# STM32G4.net
KiCad netlist of a schematic drawn in Altium Designer
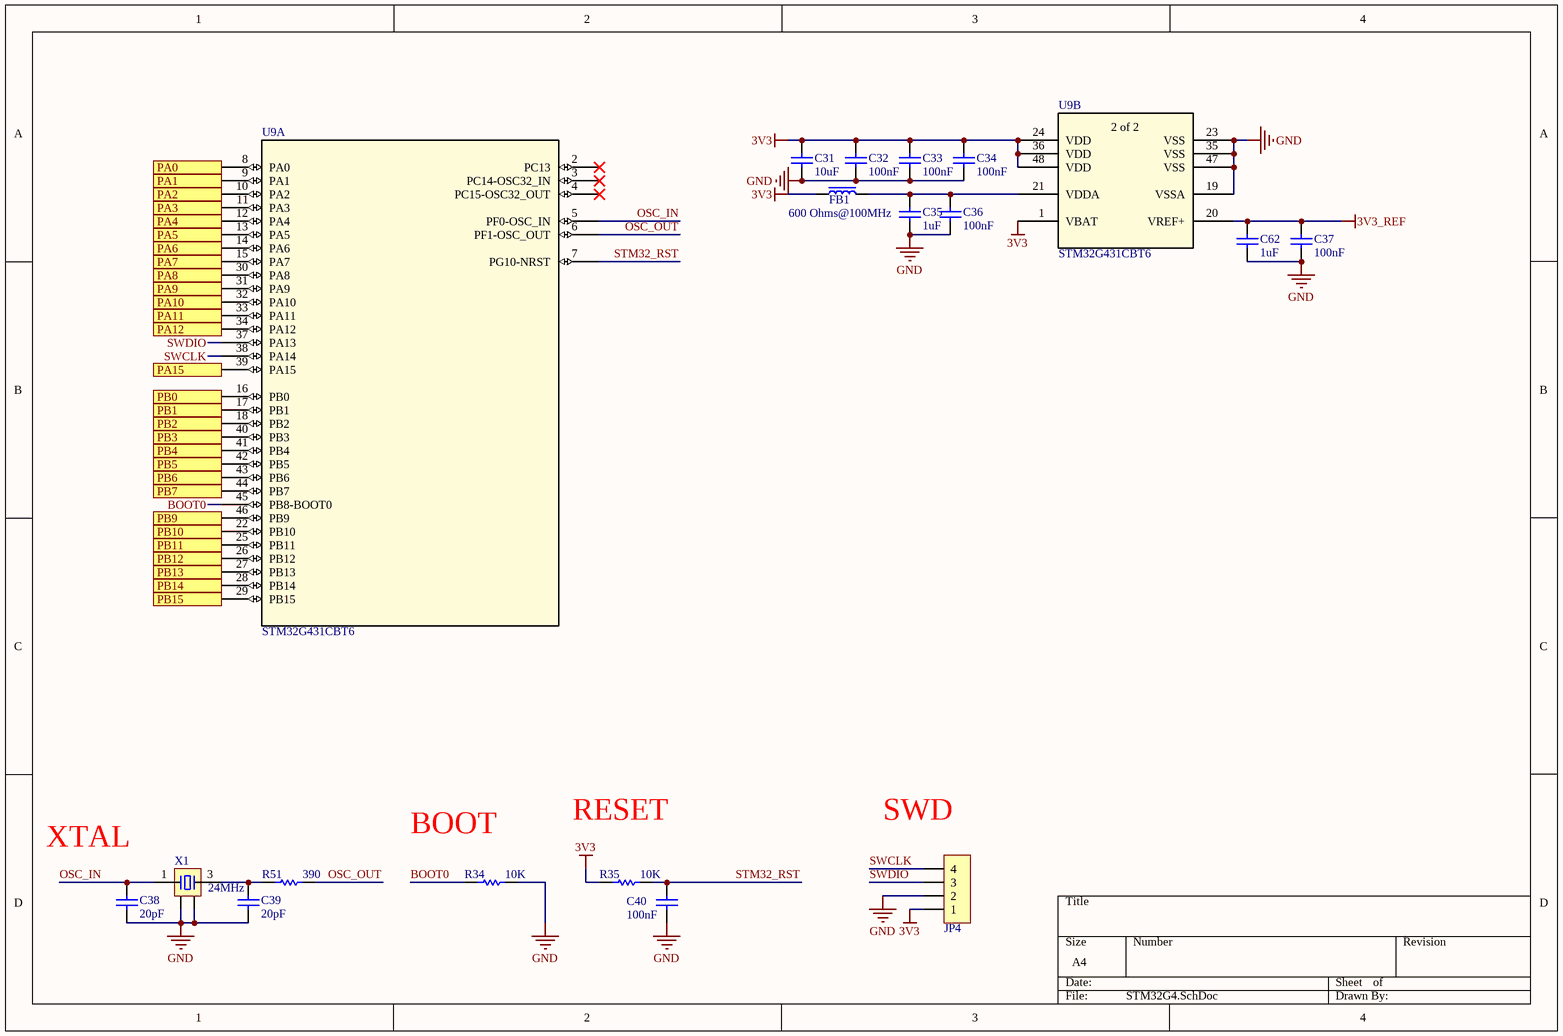
[diagram p0: STM32G4.SchDoc]

(export (version "E")
  (design (tool "Eeschema 10.0.6"))
  (components
    (comp (ref "C31") (value "10uF") (footprint "C0805") (libsource (lib "Cap") (part "Cap")))
    (comp (ref "C32") (value "100nF") (footprint "C0402") (libsource (lib "Cap") (part "Cap")))
    (comp (ref "C33") (value "100nF") (footprint "C0402") (libsource (lib "Cap") (part "Cap")))
    (comp (ref "C34") (value "100nF") (footprint "C0402") (libsource (lib "Cap") (part "Cap")))
    (comp (ref "C35") (value "1uF") (footprint "C0603") (libsource (lib "Cap") (part "Cap")))
    (comp (ref "C36") (value "100nF") (footprint "C0402") (libsource (lib "Cap") (part "Cap")))
    (comp (ref "C37") (value "100nF") (footprint "C0402") (libsource (lib "Cap") (part "Cap")))
    (comp (ref "C38") (value "20pF") (footprint "C0402") (libsource (lib "Cap") (part "Cap")))
    (comp (ref "C39") (value "20pF") (footprint "C0402") (libsource (lib "Cap") (part "Cap")))
    (comp (ref "C40") (value "100nF") (footprint "C0402") (libsource (lib "Cap") (part "Cap")))
    (comp (ref "C62") (value "1uF") (footprint "C0603") (libsource (lib "Cap") (part "Cap")))
    (comp (ref "FB1")
      (value "600 Ohms@100MHz")
      (footprint "FB 0402")
      (description "磁珠")
      (libsource (lib "All lib") (part "FB"))
    )
    (comp (ref "JP4")
      (value "HDR-1X4")
      (footprint "XH2.54-4P_H")
      (description "4P接插件")
      (fields (field (name "版权归属") "源创客"))
      (libsource (lib "All lib") (part "Header 4P"))
    )
    (comp (ref "R34") (value "10K") (footprint "R0402") (libsource (lib "Res") (part "RES")))
    (comp (ref "R35") (value "10K") (footprint "R0402") (libsource (lib "Res") (part "RES")))
    (comp (ref "R51") (value "390") (footprint "R0402") (libsource (lib "Res") (part "RES")))
    (comp (ref "U9")
      (value "STM32G431CBT6")
      (footprint "LQFP48 7X7_L")
      (description "No Description Available")
      (fields (field (name "COPYRIGHT") "Copyright (C) 2022 Ultra Librarian. All rights reserved."))
      (libsource (lib "All lib") (part "STM32G431CBT6"))
    )
    (comp (ref "X1")
      (value "24MHz")
      (footprint "XTAL-3225")
      (description "4脚晶振")
      (fields (field (name "版权归属") "源创客"))
      (libsource (lib "All lib") (part "XTAL-4"))
    )
  )
  (nets
    (net (code "1") (name "/BOOT0") (class "Default")
      (node (ref "R34") (pin "1") (pinfunction "1_1") (pintype "passive"))
      (node (ref "U9") (pin "45") (pinfunction "PB8-BOOT0_45") (pintype "bidirectional"))
    )
    (net (code "2") (name "/OSC_IN") (class "Default")
      (node (ref "C38") (pin "2") (pinfunction "2_2") (pintype "passive"))
      (node (ref "U9") (pin "5") (pinfunction "PF0-OSC_IN_5") (pintype "bidirectional"))
      (node (ref "X1") (pin "1") (pinfunction "1_1") (pintype "passive"))
    )
    (net (code "3") (name "/OSC_OUT") (class "Default")
      (node (ref "R51") (pin "2") (pinfunction "2_2") (pintype "passive"))
      (node (ref "U9") (pin "6") (pinfunction "PF1-OSC_OUT_6") (pintype "bidirectional"))
    )
    (net (code "4") (name "/PA0") (class "Default")
      (node (ref "U9") (pin "8") (pinfunction "PA0_8") (pintype "bidirectional"))
    )
    (net (code "5") (name "/PA1") (class "Default")
      (node (ref "U9") (pin "9") (pinfunction "PA1_9") (pintype "bidirectional"))
    )
    (net (code "6") (name "/PA2") (class "Default")
      (node (ref "U9") (pin "10") (pinfunction "PA2_10") (pintype "bidirectional"))
    )
    (net (code "7") (name "/PA3") (class "Default")
      (node (ref "U9") (pin "11") (pinfunction "PA3_11") (pintype "bidirectional"))
    )
    (net (code "8") (name "/PA4") (class "Default")
      (node (ref "U9") (pin "12") (pinfunction "PA4_12") (pintype "bidirectional"))
    )
    (net (code "9") (name "/PA5") (class "Default")
      (node (ref "U9") (pin "13") (pinfunction "PA5_13") (pintype "bidirectional"))
    )
    (net (code "10") (name "/PA6") (class "Default")
      (node (ref "U9") (pin "14") (pinfunction "PA6_14") (pintype "bidirectional"))
    )
    (net (code "11") (name "/PA7") (class "Default")
      (node (ref "U9") (pin "15") (pinfunction "PA7_15") (pintype "bidirectional"))
    )
    (net (code "12") (name "/PA8") (class "Default")
      (node (ref "U9") (pin "30") (pinfunction "PA8_30") (pintype "bidirectional"))
    )
    (net (code "13") (name "/PA9") (class "Default")
      (node (ref "U9") (pin "31") (pinfunction "PA9_31") (pintype "bidirectional"))
    )
    (net (code "14") (name "/PA10") (class "Default")
      (node (ref "U9") (pin "32") (pinfunction "PA10_32") (pintype "bidirectional"))
    )
    (net (code "15") (name "/PA11") (class "Default")
      (node (ref "U9") (pin "33") (pinfunction "PA11_33") (pintype "bidirectional"))
    )
    (net (code "16") (name "/PA12") (class "Default")
      (node (ref "U9") (pin "34") (pinfunction "PA12_34") (pintype "bidirectional"))
    )
    (net (code "17") (name "/PA15") (class "Default")
      (node (ref "U9") (pin "39") (pinfunction "PA15_39") (pintype "bidirectional"))
    )
    (net (code "18") (name "/PB0") (class "Default")
      (node (ref "U9") (pin "16") (pinfunction "PB0_16") (pintype "bidirectional"))
    )
    (net (code "19") (name "/PB1") (class "Default")
      (node (ref "U9") (pin "17") (pinfunction "PB1_17") (pintype "bidirectional"))
    )
    (net (code "20") (name "/PB2") (class "Default")
      (node (ref "U9") (pin "18") (pinfunction "PB2_18") (pintype "bidirectional"))
    )
    (net (code "21") (name "/PB3") (class "Default")
      (node (ref "U9") (pin "40") (pinfunction "PB3_40") (pintype "bidirectional"))
    )
    (net (code "22") (name "/PB4") (class "Default")
      (node (ref "U9") (pin "41") (pinfunction "PB4_41") (pintype "bidirectional"))
    )
    (net (code "23") (name "/PB5") (class "Default")
      (node (ref "U9") (pin "42") (pinfunction "PB5_42") (pintype "bidirectional"))
    )
    (net (code "24") (name "/PB6") (class "Default")
      (node (ref "U9") (pin "43") (pinfunction "PB6_43") (pintype "bidirectional"))
    )
    (net (code "25") (name "/PB7") (class "Default")
      (node (ref "U9") (pin "44") (pinfunction "PB7_44") (pintype "bidirectional"))
    )
    (net (code "26") (name "/PB9") (class "Default")
      (node (ref "U9") (pin "46") (pinfunction "PB9_46") (pintype "bidirectional"))
    )
    (net (code "27") (name "/PB10") (class "Default")
      (node (ref "U9") (pin "22") (pinfunction "PB10_22") (pintype "bidirectional"))
    )
    (net (code "28") (name "/PB11") (class "Default")
      (node (ref "U9") (pin "25") (pinfunction "PB11_25") (pintype "bidirectional"))
    )
    (net (code "29") (name "/PB12") (class "Default")
      (node (ref "U9") (pin "26") (pinfunction "PB12_26") (pintype "bidirectional"))
    )
    (net (code "30") (name "/PB13") (class "Default")
      (node (ref "U9") (pin "27") (pinfunction "PB13_27") (pintype "bidirectional"))
    )
    (net (code "31") (name "/PB14") (class "Default")
      (node (ref "U9") (pin "28") (pinfunction "PB14_28") (pintype "bidirectional"))
    )
    (net (code "32") (name "/PB15") (class "Default")
      (node (ref "U9") (pin "29") (pinfunction "PB15_29") (pintype "bidirectional"))
    )
    (net (code "33") (name "/STM32_RST") (class "Default")
      (node (ref "C40") (pin "2") (pinfunction "2_2") (pintype "passive"))
      (node (ref "R35") (pin "2") (pinfunction "2_2") (pintype "passive"))
      (node (ref "U9") (pin "7") (pinfunction "PG10-NRST_7") (pintype "bidirectional"))
    )
    (net (code "34") (name "/SWCLK") (class "Default")
      (node (ref "JP4") (pin "4") (pinfunction "4_4") (pintype "passive"))
      (node (ref "U9") (pin "38") (pinfunction "PA14_38") (pintype "bidirectional"))
    )
    (net (code "35") (name "/SWDIO") (class "Default")
      (node (ref "JP4") (pin "3") (pinfunction "3_3") (pintype "passive"))
      (node (ref "U9") (pin "37") (pinfunction "PA13_37") (pintype "bidirectional"))
    )
    (net (code "36") (name "3V3") (class "Default")
      (node (ref "C31") (pin "2") (pinfunction "2_2") (pintype "passive"))
      (node (ref "C32") (pin "2") (pinfunction "2_2") (pintype "passive"))
      (node (ref "C33") (pin "2") (pinfunction "2_2") (pintype "passive"))
      (node (ref "C34") (pin "2") (pinfunction "2_2") (pintype "passive"))
      (node (ref "FB1") (pin "1") (pinfunction "1_1") (pintype "passive"))
      (node (ref "JP4") (pin "1") (pinfunction "1_1") (pintype "passive"))
      (node (ref "R35") (pin "1") (pinfunction "1_1") (pintype "passive"))
      (node (ref "U9") (pin "1") (pinfunction "VBAT_1") (pintype "power_in"))
      (node (ref "U9") (pin "24") (pinfunction "VDD_24") (pintype "power_in"))
      (node (ref "U9") (pin "36") (pinfunction "VDD_36") (pintype "power_in"))
      (node (ref "U9") (pin "48") (pinfunction "VDD_48") (pintype "power_in"))
    )
    (net (code "37") (name "3V3_REF") (class "Default")
      (node (ref "C37") (pin "1") (pinfunction "1_1") (pintype "passive"))
      (node (ref "C62") (pin "1") (pinfunction "1_1") (pintype "passive"))
      (node (ref "U9") (pin "20") (pinfunction "VREF+_20") (pintype "power_in"))
    )
    (net (code "38") (name "GND") (class "Default")
      (node (ref "C31") (pin "1") (pinfunction "1_1") (pintype "passive"))
      (node (ref "C32") (pin "1") (pinfunction "1_1") (pintype "passive"))
      (node (ref "C33") (pin "1") (pinfunction "1_1") (pintype "passive"))
      (node (ref "C34") (pin "1") (pinfunction "1_1") (pintype "passive"))
      (node (ref "C35") (pin "2") (pinfunction "2_2") (pintype "passive"))
      (node (ref "C36") (pin "2") (pinfunction "2_2") (pintype "passive"))
      (node (ref "C37") (pin "2") (pinfunction "2_2") (pintype "passive"))
      (node (ref "C38") (pin "1") (pinfunction "1_1") (pintype "passive"))
      (node (ref "C39") (pin "1") (pinfunction "1_1") (pintype "passive"))
      (node (ref "C40") (pin "1") (pinfunction "1_1") (pintype "passive"))
      (node (ref "C62") (pin "2") (pinfunction "2_2") (pintype "passive"))
      (node (ref "JP4") (pin "2") (pinfunction "2_2") (pintype "passive"))
      (node (ref "R34") (pin "2") (pinfunction "2_2") (pintype "passive"))
      (node (ref "U9") (pin "19") (pinfunction "VSSA_19") (pintype "power_in"))
      (node (ref "U9") (pin "23") (pinfunction "VSS_23") (pintype "power_in"))
      (node (ref "U9") (pin "35") (pinfunction "VSS_35") (pintype "power_in"))
      (node (ref "U9") (pin "47") (pinfunction "VSS_47") (pintype "power_in"))
      (node (ref "X1") (pin "2") (pinfunction "2_2") (pintype "passive"))
      (node (ref "X1") (pin "4") (pinfunction "4_4") (pintype "passive"))
    )
    (net (code "39") (name "Net-(C39-Pad2)") (class "Default")
      (node (ref "C39") (pin "2") (pinfunction "2_2") (pintype "passive"))
      (node (ref "R51") (pin "1") (pinfunction "1_1") (pintype "passive"))
      (node (ref "X1") (pin "3") (pinfunction "3_3") (pintype "passive"))
    )
    (net (code "40") (name "Net-(U9B-VDDA)") (class "Default")
      (node (ref "C35") (pin "1") (pinfunction "1_1") (pintype "passive"))
      (node (ref "C36") (pin "1") (pinfunction "1_1") (pintype "passive"))
      (node (ref "FB1") (pin "2") (pinfunction "2_2") (pintype "passive"))
      (node (ref "U9") (pin "21") (pinfunction "VDDA_21") (pintype "power_in"))
    )
    (net (code "41") (name "unconnected-(U9A-PC13-Pad2)") (class "Default")
      (node (ref "U9") (pin "2") (pinfunction "PC13_2") (pintype "bidirectional+no_connect"))
    )
    (net (code "42") (name "unconnected-(U9A-PC14-OSC32_IN-Pad3)") (class "Default")
      (node (ref "U9") (pin "3") (pinfunction "PC14-OSC32_IN_3") (pintype "bidirectional+no_connect"))
    )
    (net (code "43") (name "unconnected-(U9A-PC15-OSC32_OUT-Pad4)") (class "Default")
      (node (ref "U9") (pin "4") (pinfunction "PC15-OSC32_OUT_4") (pintype "bidirectional+no_connect"))
    )
  )
)
